# IPMC_MACP.net
KiCad netlist of a schematic drawn in Altium Designer
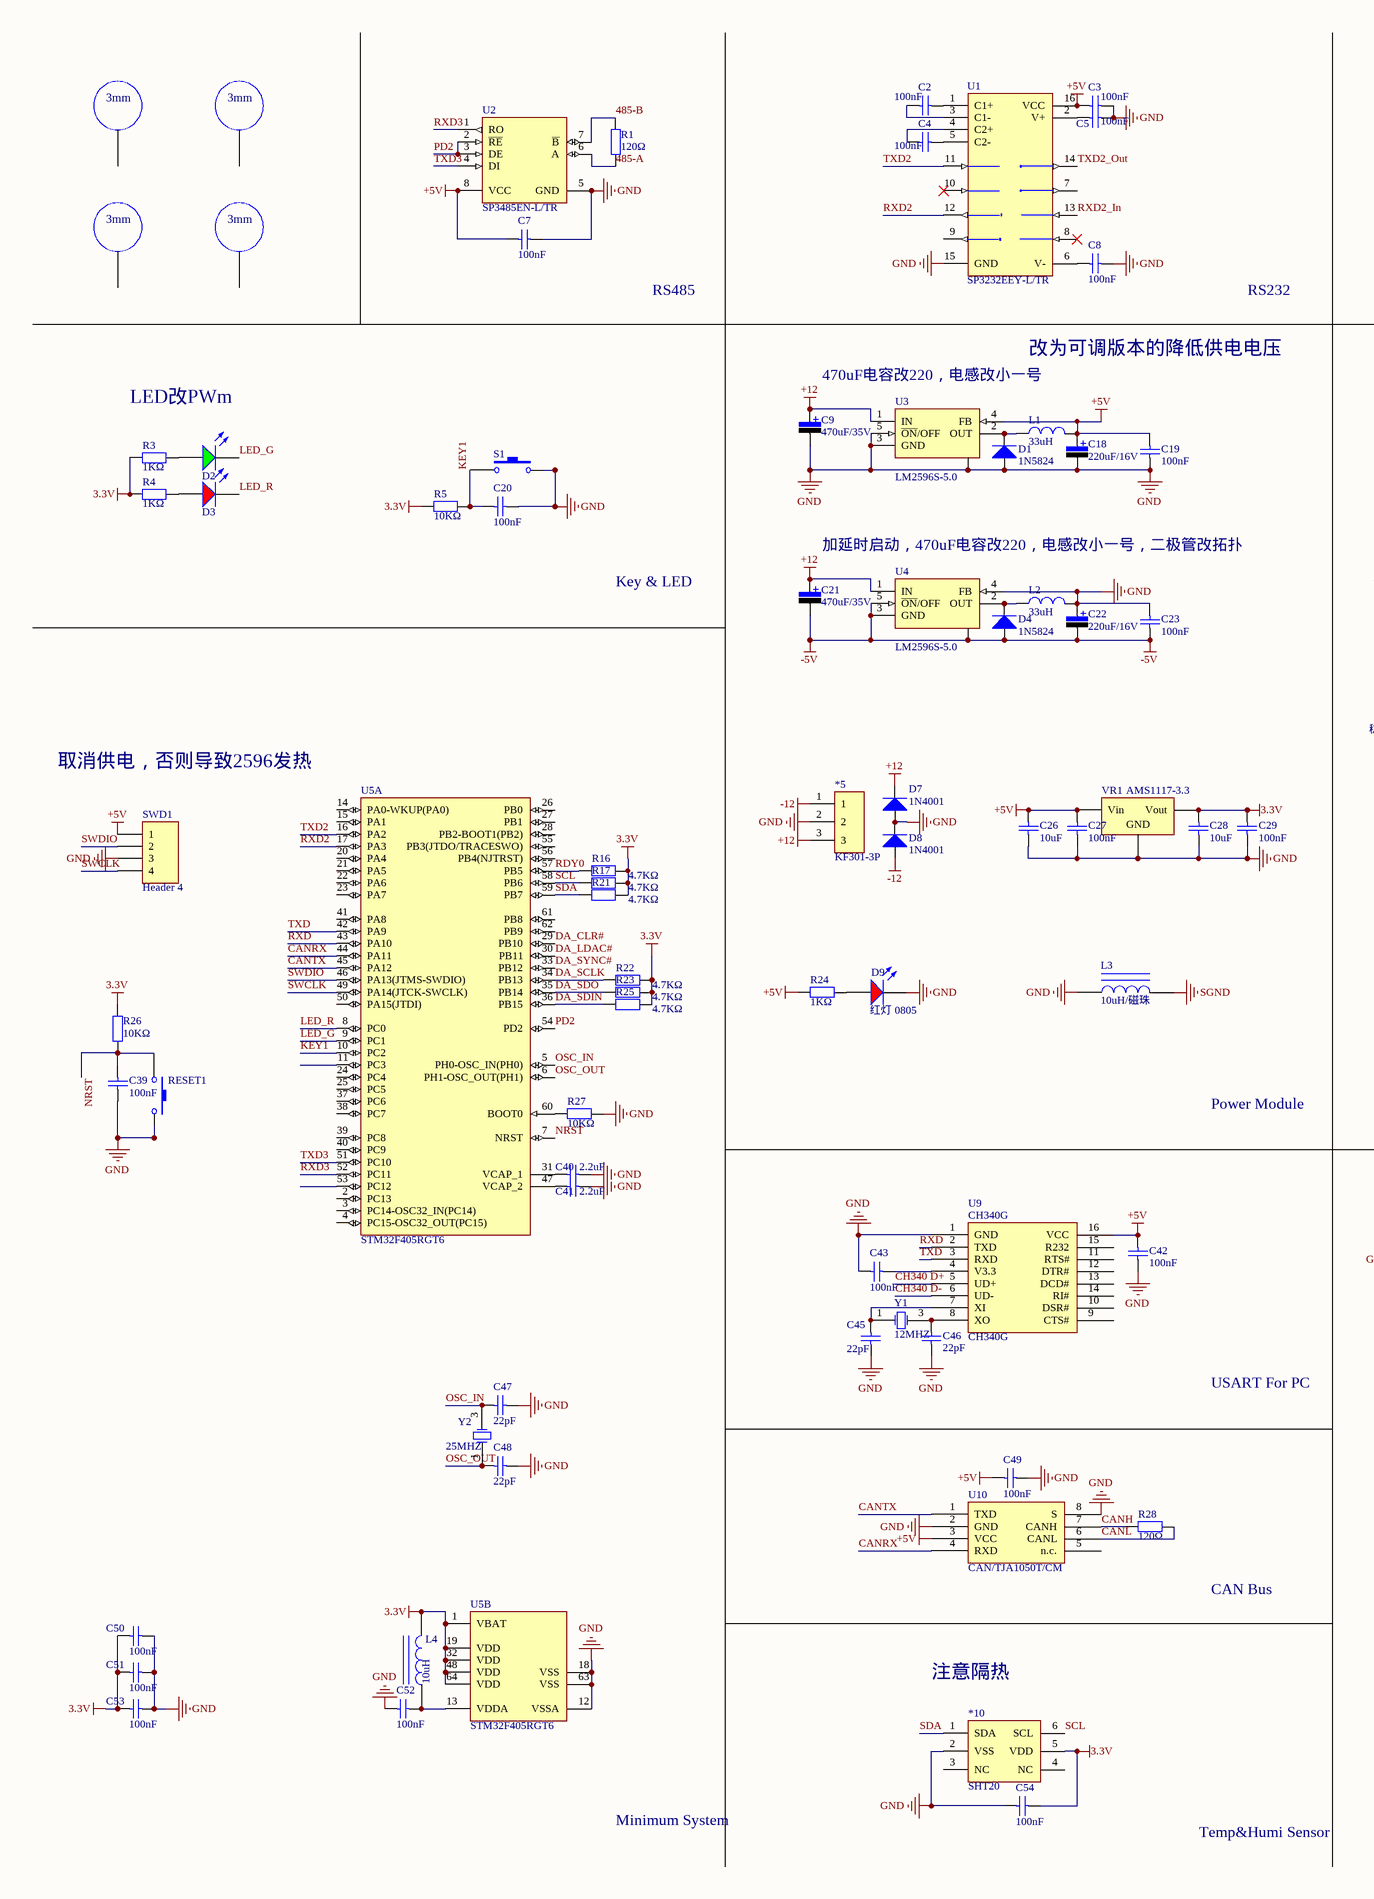
[diagram p0: IPMC_MACP.SchDoc, left]
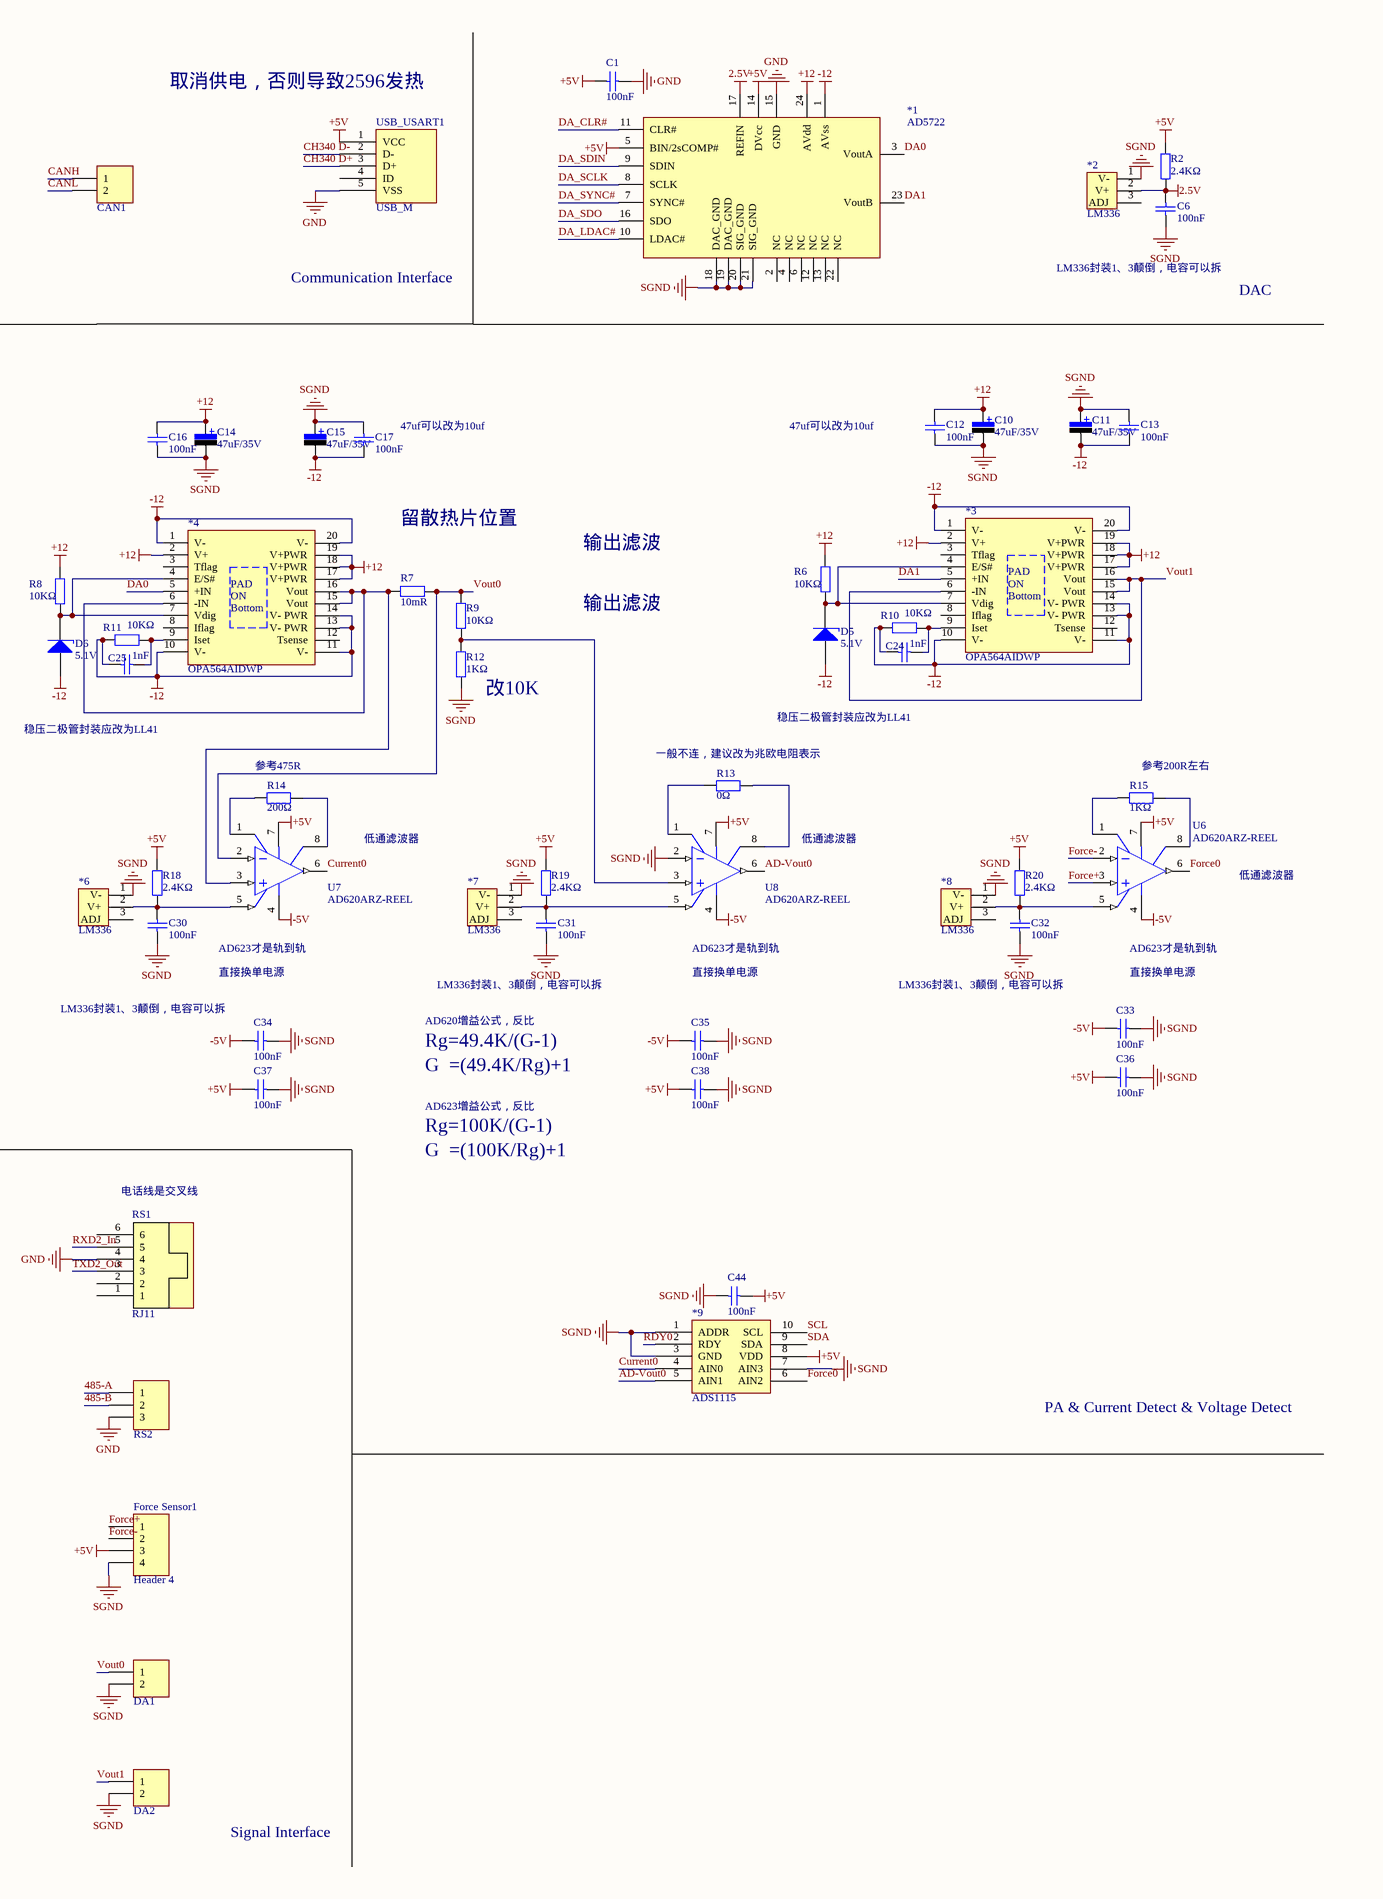
[diagram p1: IPMC_MACP.SchDoc, right]

(export (version "E")
  (design (tool "Eeschema 10.0.6"))
  (components
    (comp (ref "*1")
      (value "AD5722")
      (footprint "TSSOP24P")
      (description "双极性DAC")
      (libsource (lib "fszhang") (part "AD5722"))
    )
    (comp (ref "*2")
      (value "LM336")
      (footprint "TO-92A")
      (description "基准电压芯片2.5/5V")
      (libsource (lib "fszhang") (part "LM336"))
    )
    (comp (ref "*3")
      (value "OPA564AIDWP")
      (footprint "HSOP20")
      (description "PAD on Bottom")
      (libsource (lib "fszhang") (part "OPA564AIDWP"))
    )
    (comp (ref "*4")
      (value "OPA564AIDWP")
      (footprint "HSOP20")
      (description "PAD on Bottom")
      (libsource (lib "fszhang") (part "OPA564AIDWP"))
    )
    (comp (ref "*5")
      (value "KF301-3P")
      (footprint "KF301-3P")
      (description "蓝色端子")
      (libsource (lib "fszhang") (part "KF301-3P"))
    )
    (comp (ref "*6")
      (value "LM336")
      (footprint "TO-92A")
      (description "基准电压芯片2.5/5V")
      (libsource (lib "fszhang") (part "LM336"))
    )
    (comp (ref "*7")
      (value "LM336")
      (footprint "TO-92A")
      (description "基准电压芯片2.5/5V")
      (libsource (lib "fszhang") (part "LM336"))
    )
    (comp (ref "*8")
      (value "LM336")
      (footprint "TO-92A")
      (description "基准电压芯片2.5/5V")
      (libsource (lib "fszhang") (part "LM336"))
    )
    (comp (ref "*9") (value "ADS1115") (footprint "MSOP-UN10_N") (libsource (lib "fszhang") (part "ADS1115")))
    (comp (ref "*10") (value "SHT20") (footprint "DFN6") (libsource (lib "fszhang") (part "SHT20")))
    (comp (ref "C1")
      (value "100nF")
      (footprint "0805_C")
      (description "贴片电容")
      (libsource (lib "Miscellaneous Devices LC") (part "0805 100nF(104) 10% 50V"))
    )
    (comp (ref "C2")
      (value "100nF")
      (footprint "0805_C")
      (description "贴片电容")
      (libsource (lib "Miscellaneous Devices LC") (part "0805 100nF(104) 10% 50V"))
    )
    (comp (ref "C3")
      (value "100nF")
      (footprint "0805_C")
      (description "贴片电容")
      (libsource (lib "Miscellaneous Devices LC") (part "0805 100nF(104) 10% 50V"))
    )
    (comp (ref "C4")
      (value "100nF")
      (footprint "0805_C")
      (description "贴片电容")
      (libsource (lib "Miscellaneous Devices LC") (part "0805 100nF(104) 10% 50V"))
    )
    (comp (ref "C5")
      (value "100nF")
      (footprint "0805_C")
      (description "贴片电容")
      (libsource (lib "Miscellaneous Devices LC") (part "0805 100nF(104) 10% 50V"))
    )
    (comp (ref "C6")
      (value "100nF")
      (footprint "0805_C")
      (description "贴片电容")
      (libsource (lib "Miscellaneous Devices LC") (part "0805 100nF(104) 10% 50V"))
    )
    (comp (ref "C7")
      (value "100nF")
      (footprint "0805_C")
      (description "贴片电容")
      (libsource (lib "Miscellaneous Devices LC") (part "0805 100nF(104) 10% 50V"))
    )
    (comp (ref "C8")
      (value "100nF")
      (footprint "0805_C")
      (description "贴片电容")
      (libsource (lib "Miscellaneous Devices LC") (part "0805 100nF(104) 10% 50V"))
    )
    (comp (ref "C9")
      (value "470uF/35V")
      (footprint "C-RB-S10")
      (description "极性电解电容")
      (fields (field (name "PUBLISHER") "Altium Limited"))
      (libsource (lib "fszhang") (part "Cap Pol"))
    )
    (comp (ref "C10")
      (value "47uF/35V")
      (footprint "C-RB-S6")
      (description "极性电解电容")
      (fields (field (name "PUBLISHER") "Altium Limited"))
      (libsource (lib "fszhang") (part "Cap Pol"))
    )
    (comp (ref "C11")
      (value "47uF/35V")
      (footprint "C-RB-S6")
      (description "极性电解电容")
      (fields (field (name "PUBLISHER") "Altium Limited"))
      (libsource (lib "fszhang") (part "Cap Pol"))
    )
    (comp (ref "C12")
      (value "100nF")
      (footprint "0805_C")
      (description "贴片电容")
      (libsource (lib "Miscellaneous Devices LC") (part "0805 100nF(104) 10% 50V"))
    )
    (comp (ref "C13")
      (value "100nF")
      (footprint "0805_C")
      (description "贴片电容")
      (libsource (lib "Miscellaneous Devices LC") (part "0805 100nF(104) 10% 50V"))
    )
    (comp (ref "C14")
      (value "47uF/35V")
      (footprint "C-RB-S6")
      (description "极性电解电容")
      (fields (field (name "PUBLISHER") "Altium Limited"))
      (libsource (lib "fszhang") (part "Cap Pol"))
    )
    (comp (ref "C15")
      (value "47uF/35V")
      (footprint "C-RB-S6")
      (description "极性电解电容")
      (fields (field (name "PUBLISHER") "Altium Limited"))
      (libsource (lib "fszhang") (part "Cap Pol"))
    )
    (comp (ref "C16")
      (value "100nF")
      (footprint "0805_C")
      (description "贴片电容")
      (libsource (lib "Miscellaneous Devices LC") (part "0805 100nF(104) 10% 50V"))
    )
    (comp (ref "C17")
      (value "100nF")
      (footprint "0805_C")
      (description "贴片电容")
      (libsource (lib "Miscellaneous Devices LC") (part "0805 100nF(104) 10% 50V"))
    )
    (comp (ref "C18")
      (value "220uF/16V")
      (footprint "C-RB-S6")
      (description "极性电解电容")
      (fields (field (name "PUBLISHER") "Altium Limited"))
      (libsource (lib "fszhang") (part "Cap Pol"))
    )
    (comp (ref "C19")
      (value "100nF")
      (footprint "0805_C")
      (description "贴片电容")
      (libsource (lib "Miscellaneous Devices LC") (part "0805 100nF(104) 10% 50V"))
    )
    (comp (ref "C20")
      (value "100nF")
      (footprint "0805_C")
      (description "贴片电容")
      (libsource (lib "Miscellaneous Devices LC") (part "0805 100nF(104) 10% 50V"))
    )
    (comp (ref "C21")
      (value "470uF/35V")
      (footprint "C-RB-S10")
      (description "极性电解电容")
      (fields (field (name "PUBLISHER") "Altium Limited"))
      (libsource (lib "fszhang") (part "Cap Pol"))
    )
    (comp (ref "C22")
      (value "220uF/16V")
      (footprint "C-RB-S6")
      (description "极性电解电容")
      (fields (field (name "PUBLISHER") "Altium Limited"))
      (libsource (lib "fszhang") (part "Cap Pol"))
    )
    (comp (ref "C23")
      (value "100nF")
      (footprint "0805_C")
      (description "贴片电容")
      (libsource (lib "Miscellaneous Devices LC") (part "0805 100nF(104) 10% 50V"))
    )
    (comp (ref "C24")
      (value "1nF")
      (footprint "0805_C")
      (description "贴片电容")
      (libsource (lib "Miscellaneous Devices LC") (part "0805 1nF (102) 10% 50V"))
    )
    (comp (ref "C25")
      (value "1nF")
      (footprint "0805_C")
      (description "贴片电容")
      (libsource (lib "Miscellaneous Devices LC") (part "0805 1nF (102) 10% 50V"))
    )
    (comp (ref "C26")
      (value "10uF")
      (footprint "0805_C")
      (description "贴片电容")
      (libsource (lib "Miscellaneous Devices LC") (part "0805 10uF (106) 10% 25V"))
    )
    (comp (ref "C27")
      (value "100nF")
      (footprint "0805_C")
      (description "贴片电容")
      (libsource (lib "Miscellaneous Devices LC") (part "0805 100nF(104) 10% 50V"))
    )
    (comp (ref "C28")
      (value "10uF")
      (footprint "0805_C")
      (description "贴片电容")
      (libsource (lib "Miscellaneous Devices LC") (part "0805 10uF (106) 10% 25V"))
    )
    (comp (ref "C29")
      (value "100nF")
      (footprint "0805_C")
      (description "贴片电容")
      (libsource (lib "Miscellaneous Devices LC") (part "0805 100nF(104) 10% 50V"))
    )
    (comp (ref "C30")
      (value "100nF")
      (footprint "0805_C")
      (description "贴片电容")
      (libsource (lib "Miscellaneous Devices LC") (part "0805 100nF(104) 10% 50V"))
    )
    (comp (ref "C31")
      (value "100nF")
      (footprint "0805_C")
      (description "贴片电容")
      (libsource (lib "Miscellaneous Devices LC") (part "0805 100nF(104) 10% 50V"))
    )
    (comp (ref "C32")
      (value "100nF")
      (footprint "0805_C")
      (description "贴片电容")
      (libsource (lib "Miscellaneous Devices LC") (part "0805 100nF(104) 10% 50V"))
    )
    (comp (ref "C33")
      (value "100nF")
      (footprint "0805_C")
      (description "贴片电容")
      (libsource (lib "Miscellaneous Devices LC") (part "0805 100nF(104) 10% 50V"))
    )
    (comp (ref "C34")
      (value "100nF")
      (footprint "0805_C")
      (description "贴片电容")
      (libsource (lib "Miscellaneous Devices LC") (part "0805 100nF(104) 10% 50V"))
    )
    (comp (ref "C35")
      (value "100nF")
      (footprint "0805_C")
      (description "贴片电容")
      (libsource (lib "Miscellaneous Devices LC") (part "0805 100nF(104) 10% 50V"))
    )
    (comp (ref "C36")
      (value "100nF")
      (footprint "0805_C")
      (description "贴片电容")
      (libsource (lib "Miscellaneous Devices LC") (part "0805 100nF(104) 10% 50V"))
    )
    (comp (ref "C37")
      (value "100nF")
      (footprint "0805_C")
      (description "贴片电容")
      (libsource (lib "Miscellaneous Devices LC") (part "0805 100nF(104) 10% 50V"))
    )
    (comp (ref "C38")
      (value "100nF")
      (footprint "0805_C")
      (description "贴片电容")
      (libsource (lib "Miscellaneous Devices LC") (part "0805 100nF(104) 10% 50V"))
    )
    (comp (ref "C39")
      (value "100nF")
      (footprint "0805_C")
      (description "贴片电容")
      (libsource (lib "Miscellaneous Devices LC") (part "0805 100nF(104) 10% 50V"))
    )
    (comp (ref "C40")
      (value "2.2uF")
      (footprint "0805_C")
      (description "贴片电容")
      (libsource (lib "Miscellaneous Devices LC") (part "0805 2.2uF (225) 20% 50V"))
    )
    (comp (ref "C41")
      (value "2.2uF")
      (footprint "0805_C")
      (description "贴片电容")
      (libsource (lib "Miscellaneous Devices LC") (part "0805 2.2uF (225) 20% 50V"))
    )
    (comp (ref "C42")
      (value "100nF")
      (footprint "0805_C")
      (description "贴片电容")
      (libsource (lib "Miscellaneous Devices LC") (part "0805 100nF(104) 10% 50V"))
    )
    (comp (ref "C43")
      (value "100nF")
      (footprint "0805_C")
      (description "贴片电容")
      (libsource (lib "Miscellaneous Devices LC") (part "0805 100nF(104) 10% 50V"))
    )
    (comp (ref "C44")
      (value "100nF")
      (footprint "0805_C")
      (description "贴片电容")
      (libsource (lib "Miscellaneous Devices LC") (part "0805 100nF(104) 10% 50V"))
    )
    (comp (ref "C45")
      (value "22pF")
      (footprint "0805_C")
      (description "贴片电容")
      (libsource (lib "Miscellaneous Devices LC") (part "0805 22pF (220) 5% 50V"))
    )
    (comp (ref "C46")
      (value "22pF")
      (footprint "0805_C")
      (description "贴片电容")
      (libsource (lib "Miscellaneous Devices LC") (part "0805 22pF (220) 5% 50V"))
    )
    (comp (ref "C47")
      (value "22pF")
      (footprint "0805_C")
      (description "贴片电容")
      (libsource (lib "Miscellaneous Devices LC") (part "0805 22pF (220) 5% 50V"))
    )
    (comp (ref "C48")
      (value "22pF")
      (footprint "0805_C")
      (description "贴片电容")
      (libsource (lib "Miscellaneous Devices LC") (part "0805 22pF (220) 5% 50V"))
    )
    (comp (ref "C49")
      (value "100nF")
      (footprint "0805_C")
      (description "贴片电容")
      (libsource (lib "Miscellaneous Devices LC") (part "0805 100nF(104) 10% 50V"))
    )
    (comp (ref "C50")
      (value "100nF")
      (footprint "0805_C")
      (description "贴片电容")
      (libsource (lib "Miscellaneous Devices LC") (part "0805 100nF(104) 10% 50V"))
    )
    (comp (ref "C51")
      (value "100nF")
      (footprint "0805_C")
      (description "贴片电容")
      (libsource (lib "Miscellaneous Devices LC") (part "0805 100nF(104) 10% 50V"))
    )
    (comp (ref "C52")
      (value "100nF")
      (footprint "0805_C")
      (description "贴片电容")
      (libsource (lib "Miscellaneous Devices LC") (part "0805 100nF(104) 10% 50V"))
    )
    (comp (ref "C53")
      (value "100nF")
      (footprint "0805_C")
      (description "贴片电容")
      (libsource (lib "Miscellaneous Devices LC") (part "0805 100nF(104) 10% 50V"))
    )
    (comp (ref "C54")
      (value "100nF")
      (footprint "0805_C")
      (description "贴片电容")
      (libsource (lib "Miscellaneous Devices LC") (part "0805 100nF(104) 10% 50V"))
    )
    (comp (ref "CAN1")
      (value "Header 2")
      (footprint "HDR2X1_B1")
      (description "接插件")
      (fields (field (name "PUBLISHER") "Altium Limited"))
      (libsource (lib "fszhang") (part "Header 2"))
    )
    (comp (ref "D1")
      (value "1N5824")
      (footprint "DIODE-SMA")
      (description "二极管")
      (fields (field (name "PUBLISHER") "Altium Limited"))
      (libsource (lib "fszhang") (part "Diode"))
    )
    (comp (ref "D2")
      (value "翠绿 0805")
      (footprint "0805_LED_S1")
      (description "发光二极管")
      (libsource (lib "Miscellaneous Devices LC") (part "0805 翠绿"))
    )
    (comp (ref "D3")
      (value "红灯 0805")
      (footprint "0805_LED_S1")
      (description "发光二极管")
      (libsource (lib "Miscellaneous Devices LC") (part "0805 红灯"))
    )
    (comp (ref "D4")
      (value "1N5824")
      (footprint "DIODE-SMA")
      (description "二极管")
      (fields (field (name "PUBLISHER") "Altium Limited"))
      (libsource (lib "fszhang") (part "Diode"))
    )
    (comp (ref "D5")
      (value "5.1V")
      (footprint "DIODE-1206")
      (description "稳压二极管")
      (fields (field (name "PUBLISHER") "Altium Limited"))
      (libsource (lib "fszhang") (part "Diode-Z"))
    )
    (comp (ref "D6")
      (value "5.1V")
      (footprint "DIODE-1206")
      (description "稳压二极管")
      (fields (field (name "PUBLISHER") "Altium Limited"))
      (libsource (lib "fszhang") (part "Diode-Z"))
    )
    (comp (ref "D7")
      (value "1N4001")
      (footprint "DIODE-SMA")
      (description "二极管")
      (fields (field (name "PUBLISHER") "Altium Limited"))
      (libsource (lib "fszhang") (part "Diode"))
    )
    (comp (ref "D8")
      (value "1N4001")
      (footprint "DIODE-SMA")
      (description "二极管")
      (fields (field (name "PUBLISHER") "Altium Limited"))
      (libsource (lib "fszhang") (part "Diode"))
    )
    (comp (ref "D9")
      (value "红灯 0805")
      (footprint "0805_LED_S1")
      (description "发光二极管")
      (libsource (lib "Miscellaneous Devices LC") (part "0805 红灯"))
    )
    (comp (ref "DA1")
      (value "Header 2")
      (footprint "HDR2X1_B1")
      (description "接插件")
      (fields (field (name "PUBLISHER") "Altium Limited"))
      (libsource (lib "fszhang") (part "Header 2"))
    )
    (comp (ref "DA2")
      (value "Header 2")
      (footprint "HDR2X1_B1")
      (description "接插件")
      (fields (field (name "PUBLISHER") "Altium Limited"))
      (libsource (lib "fszhang") (part "Header 2"))
    )
    (comp (ref "Force Sensor1")
      (value "Header 4")
      (footprint "fszhang:HDR4X1_B1")
      (description "Header, 4-Pin")
      (fields (field (name "PUBLISHER") "Altium Limited"))
      (libsource (lib "Miscellaneous Connectors") (part "Header 4"))
    )
    (comp (ref "L1")
      (value "33uH")
      (footprint "L-SMD-12")
      (description "电感")
      (fields (field (name "PUBLISHER") "Altium Limited"))
      (libsource (lib "fszhang") (part "Inductor"))
    )
    (comp (ref "L2")
      (value "33uH")
      (footprint "L-SMD-12")
      (description "电感")
      (fields (field (name "PUBLISHER") "Altium Limited"))
      (libsource (lib "fszhang") (part "Inductor"))
    )
    (comp (ref "L3")
      (value "10uH/磁珠")
      (footprint "0805_L")
      (description "贴片电感")
      (libsource (lib "Miscellaneous Devices LC") (part "0805 10uH 10%"))
    )
    (comp (ref "L4")
      (value "10uH")
      (footprint "0805_L")
      (description "贴片电感")
      (libsource (lib "Miscellaneous Devices LC") (part "0805 10uH 10%"))
    )
    (comp (ref "R1")
      (value "120Ω")
      (footprint "0805_R")
      (description "贴片电阻")
      (libsource (lib "") (part "0805 120Ω (1200) 1%_1"))
    )
    (comp (ref "R2")
      (value "2.4KΩ")
      (footprint "0805_R")
      (description "贴片电阻")
      (libsource (lib "Miscellaneous Devices LC") (part "0805 2.4KΩ (2401) 1%"))
    )
    (comp (ref "R3")
      (value "1KΩ")
      (footprint "0805_R")
      (description "贴片电阻")
      (libsource (lib "Miscellaneous Devices LC") (part "0805 1KΩ (1001) 1%"))
    )
    (comp (ref "R4")
      (value "1KΩ")
      (footprint "0805_R")
      (description "贴片电阻")
      (libsource (lib "Miscellaneous Devices LC") (part "0805 1KΩ (1001) 1%"))
    )
    (comp (ref "R5")
      (value "10KΩ")
      (footprint "0805_R")
      (description "贴片电阻")
      (libsource (lib "Miscellaneous Devices LC") (part "0805 10KΩ (1002) 1%"))
    )
    (comp (ref "R6")
      (value "10KΩ")
      (footprint "0805_R")
      (description "贴片电阻")
      (libsource (lib "") (part "0805 10KΩ (1002) 1%_3"))
    )
    (comp (ref "R7")
      (value "10mR")
      (footprint "2512")
      (description "贴片电阻")
      (fields (field (name "PUBLISHER") "Altium Limited"))
      (libsource (lib "fszhang") (part "Res1"))
    )
    (comp (ref "R8")
      (value "10KΩ")
      (footprint "0805_R")
      (description "贴片电阻")
      (libsource (lib "") (part "0805 10KΩ (1002) 1%_3"))
    )
    (comp (ref "R9")
      (value "10KΩ")
      (footprint "0805_R")
      (description "贴片电阻")
      (libsource (lib "Miscellaneous Devices LC") (part "0805 20KΩ (2002) 1%"))
    )
    (comp (ref "R10")
      (value "10KΩ")
      (footprint "0805_R")
      (description "贴片电阻")
      (libsource (lib "Miscellaneous Devices LC") (part "0805 10KΩ (1002) 1%"))
    )
    (comp (ref "R11")
      (value "10KΩ")
      (footprint "0805_R")
      (description "贴片电阻")
      (libsource (lib "Miscellaneous Devices LC") (part "0805 10KΩ (1002) 1%"))
    )
    (comp (ref "R12")
      (value "1KΩ")
      (footprint "0805_R")
      (description "贴片电阻")
      (libsource (lib "Miscellaneous Devices LC") (part "0805 20KΩ (2002) 1%"))
    )
    (comp (ref "R13")
      (value "0Ω")
      (footprint "0805_R")
      (description "贴片电阻")
      (libsource (lib "Miscellaneous Devices LC") (part "0805 0Ω (0R0) 1%"))
    )
    (comp (ref "R14")
      (value "200Ω")
      (footprint "0805_R")
      (description "贴片电阻")
      (libsource (lib "Miscellaneous Devices LC") (part "0805 200Ω (2000) 1%"))
    )
    (comp (ref "R15")
      (value "1KΩ")
      (footprint "0805_R")
      (description "贴片电阻")
      (libsource (lib "Miscellaneous Devices LC") (part "0805 1KΩ (1001) 1%"))
    )
    (comp (ref "R16")
      (value "4.7KΩ")
      (footprint "0805_R")
      (description "贴片电阻")
      (libsource (lib "Miscellaneous Devices LC") (part "0805 4.7KΩ (4701) 1%"))
    )
    (comp (ref "R17")
      (value "4.7KΩ")
      (footprint "0805_R")
      (description "贴片电阻")
      (libsource (lib "Miscellaneous Devices LC") (part "0805 4.7KΩ (4701) 1%"))
    )
    (comp (ref "R18")
      (value "2.4KΩ")
      (footprint "0805_R")
      (description "贴片电阻")
      (libsource (lib "Miscellaneous Devices LC") (part "0805 2.4KΩ (2401) 1%"))
    )
    (comp (ref "R19")
      (value "2.4KΩ")
      (footprint "0805_R")
      (description "贴片电阻")
      (libsource (lib "Miscellaneous Devices LC") (part "0805 2.4KΩ (2401) 1%"))
    )
    (comp (ref "R20")
      (value "2.4KΩ")
      (footprint "0805_R")
      (description "贴片电阻")
      (libsource (lib "Miscellaneous Devices LC") (part "0805 2.4KΩ (2401) 1%"))
    )
    (comp (ref "R21")
      (value "4.7KΩ")
      (footprint "0805_R")
      (description "贴片电阻")
      (libsource (lib "Miscellaneous Devices LC") (part "0805 4.7KΩ (4701) 1%"))
    )
    (comp (ref "R22")
      (value "4.7KΩ")
      (footprint "0805_R")
      (description "贴片电阻")
      (libsource (lib "Miscellaneous Devices LC") (part "0805 4.7KΩ (4701) 1%"))
    )
    (comp (ref "R23")
      (value "4.7KΩ")
      (footprint "0805_R")
      (description "贴片电阻")
      (libsource (lib "Miscellaneous Devices LC") (part "0805 4.7KΩ (4701) 1%"))
    )
    (comp (ref "R24")
      (value "1KΩ")
      (footprint "0805_R")
      (description "贴片电阻")
      (libsource (lib "Miscellaneous Devices LC") (part "0805 1KΩ (1001) 1%"))
    )
    (comp (ref "R25")
      (value "4.7KΩ")
      (footprint "0805_R")
      (description "贴片电阻")
      (libsource (lib "Miscellaneous Devices LC") (part "0805 4.7KΩ (4701) 1%"))
    )
    (comp (ref "R26")
      (value "10KΩ")
      (footprint "0805_R")
      (description "贴片电阻")
      (libsource (lib "") (part "0805 10KΩ (1002) 1%_1"))
    )
    (comp (ref "R27")
      (value "10KΩ")
      (footprint "0805_R")
      (description "贴片电阻")
      (libsource (lib "") (part "0805 10KΩ (1002) 1%_2"))
    )
    (comp (ref "R28")
      (value "120Ω")
      (footprint "0805_R")
      (description "贴片电阻")
      (libsource (lib "Miscellaneous Devices LC") (part "0805 120Ω (1200) 1%"))
    )
    (comp (ref "RESET1")
      (value "SW-PB")
      (footprint "SW_PB2_A1")
      (description "微动开关")
      (fields (field (name "PUBLISHER") "Altium Limited"))
      (libsource (lib "fszhang") (part "SW-PB"))
    )
    (comp (ref "RS1") (value "RJ11") (footprint "RJ6-RJ11") (libsource (lib "fszhang") (part "RJ11")))
    (comp (ref "RS2")
      (value "Header 3")
      (footprint "HDR3X1_B1")
      (description "接插件")
      (fields (field (name "PUBLISHER") "Altium Limited"))
      (libsource (lib "fszhang") (part "Header 3"))
    )
    (comp (ref "S1")
      (value "SW-PB")
      (footprint "SW_PB2_A1")
      (description "微动开关")
      (fields (field (name "PUBLISHER") "Altium Limited"))
      (libsource (lib "fszhang") (part "SW-PB"))
    )
    (comp (ref "SWD1")
      (value "Header 4")
      (footprint "HDR1X4")
      (description "Header, 4-Pin")
      (fields (field (name "PUBLISHER") "Altium Limited"))
      (libsource (lib "Miscellaneous Connectors") (part "Header 4"))
    )
    (comp (ref "T1") (value "M3铜柱螺丝孔") (footprint "螺丝孔-3mm") (libsource (lib "fszhang") (part "M3铜柱螺丝孔")))
    (comp (ref "T2") (value "M3铜柱螺丝孔") (footprint "螺丝孔-3mm") (libsource (lib "fszhang") (part "M3铜柱螺丝孔")))
    (comp (ref "T3") (value "M3铜柱螺丝孔") (footprint "螺丝孔-3mm") (libsource (lib "fszhang") (part "M3铜柱螺丝孔")))
    (comp (ref "T4") (value "M3铜柱螺丝孔") (footprint "螺丝孔-3mm") (libsource (lib "fszhang") (part "M3铜柱螺丝孔")))
    (comp (ref "U1")
      (value "SP3232EEY-L/TR")
      (footprint "TSSOP-16")
      (description "RS232")
      (libsource (lib "Miscellaneous Devices LC") (part "SP3232EEY-L/TR"))
    )
    (comp (ref "U2")
      (value "SP3485EN-L/TR")
      (footprint "SOIC-8_150mil")
      (description "RS-485/RS-422")
      (libsource (lib "Miscellaneous Devices LC") (part "SP3485EN-L/TR"))
    )
    (comp (ref "U3")
      (value "LM2596S-5.0")
      (footprint "TO-263-5")
      (description "5V稳压芯片")
      (fields (field (name "PUBLISHER") "Altium Limited"))
      (libsource (lib "fszhang") (part "LM2596S-5.0"))
    )
    (comp (ref "U4")
      (value "LM2596S-5.0")
      (footprint "TO-263-5")
      (description "5V稳压芯片")
      (fields (field (name "PUBLISHER") "Altium Limited"))
      (libsource (lib "fszhang") (part "LM2596S-5.0"))
    )
    (comp (ref "U5")
      (value "STM32F405RGT6")
      (footprint "STM-LQFP64_L")
      (fields (field (name "MANUFACTURER") "STMicroelectronics"))
      (libsource (lib "STMicroelectronics STM32 F4") (part "STM32F405RGT6"))
    )
    (comp (ref "U6")
      (value "AD620ARZ-REEL")
      (footprint "SOIC-8_150mil")
      (description "仪放")
      (libsource (lib "Miscellaneous Devices LC") (part "AD620ARZ-REEL"))
    )
    (comp (ref "U7")
      (value "AD620ARZ-REEL")
      (footprint "SOIC-8_150mil")
      (description "仪放")
      (libsource (lib "Miscellaneous Devices LC") (part "AD620ARZ-REEL"))
    )
    (comp (ref "U8")
      (value "AD620ARZ-REEL")
      (footprint "SOIC-8_150mil")
      (description "仪放")
      (libsource (lib "Miscellaneous Devices LC") (part "AD620ARZ-REEL"))
    )
    (comp (ref "U9")
      (value "CH340G")
      (footprint "SOIC-16_150mil")
      (description "USB")
      (libsource (lib "Miscellaneous Devices LC") (part "CH340G"))
    )
    (comp (ref "U10")
      (value "CAN/TJA1050T/CM")
      (footprint "SOIC-8_150mil")
      (description "CAN")
      (libsource (lib "Miscellaneous Devices LC") (part "CAN/TJA1050T/CM"))
    )
    (comp (ref "USB_USART1")
      (value "USB_M")
      (footprint "USB_MICRO")
      (description "MicroUSB接口")
      (libsource (lib "fszhang") (part "USB_M"))
    )
    (comp (ref "VR1")
      (value "AMS1117-3.3")
      (footprint "SOT-223")
      (description "低压差线性稳压(LDO)")
      (libsource (lib "Miscellaneous Devices LC") (part "SOT-223 AMS1117-3.3"))
    )
    (comp (ref "Y1")
      (value "12MHZ")
      (footprint "SMD-3225_4P")
      (description "贴片晶振")
      (libsource (lib "Miscellaneous Devices LC") (part "SMD-3225_4P  12MHZ 20PF 10PPM"))
    )
    (comp (ref "Y2")
      (value "25MHZ")
      (footprint "SMD-3225_4P")
      (description "贴片晶振")
      (libsource (lib "Miscellaneous Devices LC") (part "SMD-3225_4P  25MHZ 12PF 10PPM"))
    )
  )
  (nets
    (net (code "1") (name "+5V") (class "Default")
      (node (ref "*1") (pin "14") (pinfunction "DVcc_14") (pintype "passive"))
      (node (ref "*1") (pin "5") (pinfunction "BIN/2sCOMP#_5") (pintype "passive"))
      (node (ref "*9") (pin "8") (pinfunction "VDD_8") (pintype "passive"))
      (node (ref "C1") (pin "2") (pinfunction "2_2") (pintype "passive"))
      (node (ref "C18") (pin "1") (pinfunction "1_1") (pintype "passive"))
      (node (ref "C19") (pin "2") (pinfunction "2_2") (pintype "passive"))
      (node (ref "C26") (pin "2") (pinfunction "2_2") (pintype "passive"))
      (node (ref "C27") (pin "2") (pinfunction "2_2") (pintype "passive"))
      (node (ref "C3") (pin "1") (pinfunction "1_1") (pintype "passive"))
      (node (ref "C36") (pin "2") (pinfunction "2_2") (pintype "passive"))
      (node (ref "C37") (pin "2") (pinfunction "2_2") (pintype "passive"))
      (node (ref "C38") (pin "2") (pinfunction "2_2") (pintype "passive"))
      (node (ref "C42") (pin "2") (pinfunction "2_2") (pintype "passive"))
      (node (ref "C44") (pin "1") (pinfunction "1_1") (pintype "passive"))
      (node (ref "C49") (pin "2") (pinfunction "2_2") (pintype "passive"))
      (node (ref "C7") (pin "2") (pinfunction "2_2") (pintype "passive"))
      (node (ref "Force Sensor1") (pin "3") (pinfunction "3_3") (pintype "passive"))
      (node (ref "L1") (pin "2") (pinfunction "2_2") (pintype "passive"))
      (node (ref "R18") (pin "2") (pinfunction "2_2") (pintype "passive"))
      (node (ref "R19") (pin "2") (pinfunction "2_2") (pintype "passive"))
      (node (ref "R2") (pin "2") (pinfunction "2_2") (pintype "passive"))
      (node (ref "R20") (pin "2") (pinfunction "2_2") (pintype "passive"))
      (node (ref "R24") (pin "1") (pinfunction "1_1") (pintype "passive"))
      (node (ref "SWD1") (pin "1") (pinfunction "1_1") (pintype "passive"))
      (node (ref "U1") (pin "16") (pinfunction "VCC_16") (pintype "power_in"))
      (node (ref "U10") (pin "3") (pinfunction "VCC_3") (pintype "passive"))
      (node (ref "U2") (pin "8") (pinfunction "VCC_8") (pintype "power_in"))
      (node (ref "U3") (pin "4") (pinfunction "FB_4") (pintype "input"))
      (node (ref "U6") (pin "7") (pinfunction "V+_7") (pintype "power_in"))
      (node (ref "U7") (pin "7") (pinfunction "V+_7") (pintype "power_in"))
      (node (ref "U8") (pin "7") (pinfunction "V+_7") (pintype "power_in"))
      (node (ref "U9") (pin "16") (pinfunction "VCC_16") (pintype "passive"))
      (node (ref "USB_USART1") (pin "1") (pinfunction "VCC_1") (pintype "passive"))
      (node (ref "VR1") (pin "3") (pinfunction "Vin_3") (pintype "passive"))
    )
    (net (code "2") (name "+12") (class "Default")
      (node (ref "*1") (pin "24") (pinfunction "AVdd_24") (pintype "passive"))
      (node (ref "*3") (pin "17") (pinfunction "V+PWR_17") (pintype "passive"))
      (node (ref "*3") (pin "18") (pinfunction "V+PWR_18") (pintype "passive"))
      (node (ref "*3") (pin "19") (pinfunction "V+PWR_19") (pintype "passive"))
      (node (ref "*3") (pin "2") (pinfunction "V+_2") (pintype "passive"))
      (node (ref "*4") (pin "17") (pinfunction "V+PWR_17") (pintype "passive"))
      (node (ref "*4") (pin "18") (pinfunction "V+PWR_18") (pintype "passive"))
      (node (ref "*4") (pin "19") (pinfunction "V+PWR_19") (pintype "passive"))
      (node (ref "*4") (pin "2") (pinfunction "V+_2") (pintype "passive"))
      (node (ref "*5") (pin "3") (pinfunction "3_3") (pintype "passive"))
      (node (ref "C10") (pin "1") (pinfunction "1_1") (pintype "passive"))
      (node (ref "C12") (pin "2") (pinfunction "2_2") (pintype "passive"))
      (node (ref "C14") (pin "1") (pinfunction "1_1") (pintype "passive"))
      (node (ref "C16") (pin "2") (pinfunction "2_2") (pintype "passive"))
      (node (ref "C21") (pin "1") (pinfunction "1_1") (pintype "passive"))
      (node (ref "C9") (pin "1") (pinfunction "1_1") (pintype "passive"))
      (node (ref "D7") (pin "2") (pinfunction "K_2") (pintype "passive"))
      (node (ref "R6") (pin "2") (pinfunction "2_2") (pintype "passive"))
      (node (ref "R8") (pin "2") (pinfunction "2_2") (pintype "passive"))
      (node (ref "U3") (pin "1") (pinfunction "IN_1") (pintype "power_in"))
      (node (ref "U4") (pin "1") (pinfunction "IN_1") (pintype "power_in"))
    )
    (net (code "3") (name "-5V") (class "Default")
      (node (ref "C21") (pin "2") (pinfunction "2_2") (pintype "passive"))
      (node (ref "C22") (pin "2") (pinfunction "2_2") (pintype "passive"))
      (node (ref "C23") (pin "1") (pinfunction "1_1") (pintype "passive"))
      (node (ref "C33") (pin "2") (pinfunction "2_2") (pintype "passive"))
      (node (ref "C34") (pin "2") (pinfunction "2_2") (pintype "passive"))
      (node (ref "C35") (pin "2") (pinfunction "2_2") (pintype "passive"))
      (node (ref "D4") (pin "1") (pinfunction "A_1") (pintype "passive"))
      (node (ref "U4") (pin "3") (pinfunction "GND_3") (pintype "power_in"))
      (node (ref "U4") (pin "5") (pinfunction "~{ON}/OFF_5") (pintype "input"))
      (node (ref "U4") (pin "6") (pinfunction "6_6") (pintype "power_in"))
      (node (ref "U6") (pin "4") (pinfunction "V-_4") (pintype "power_in"))
      (node (ref "U7") (pin "4") (pinfunction "V-_4") (pintype "power_in"))
      (node (ref "U8") (pin "4") (pinfunction "V-_4") (pintype "power_in"))
    )
    (net (code "4") (name "-12") (class "Default")
      (node (ref "*1") (pin "1") (pinfunction "AVss_1") (pintype "passive"))
      (node (ref "*3") (pin "1") (pinfunction "V-_1") (pintype "passive"))
      (node (ref "*3") (pin "10") (pinfunction "V-_10") (pintype "passive"))
      (node (ref "*3") (pin "11") (pinfunction "V-_11") (pintype "passive"))
      (node (ref "*3") (pin "13") (pinfunction "V-_PWR_13") (pintype "passive"))
      (node (ref "*3") (pin "14") (pinfunction "V-_PWR_14") (pintype "passive"))
      (node (ref "*3") (pin "20") (pinfunction "V-_20") (pintype "passive"))
      (node (ref "*4") (pin "1") (pinfunction "V-_1") (pintype "passive"))
      (node (ref "*4") (pin "10") (pinfunction "V-_10") (pintype "passive"))
      (node (ref "*4") (pin "11") (pinfunction "V-_11") (pintype "passive"))
      (node (ref "*4") (pin "13") (pinfunction "V-_PWR_13") (pintype "passive"))
      (node (ref "*4") (pin "14") (pinfunction "V-_PWR_14") (pintype "passive"))
      (node (ref "*4") (pin "20") (pinfunction "V-_20") (pintype "passive"))
      (node (ref "*5") (pin "1") (pinfunction "1_1") (pintype "passive"))
      (node (ref "C11") (pin "2") (pinfunction "2_2") (pintype "passive"))
      (node (ref "C13") (pin "2") (pinfunction "2_2") (pintype "passive"))
      (node (ref "C15") (pin "2") (pinfunction "2_2") (pintype "passive"))
      (node (ref "C17") (pin "2") (pinfunction "2_2") (pintype "passive"))
      (node (ref "C24") (pin "1") (pinfunction "1_1") (pintype "passive"))
      (node (ref "C25") (pin "1") (pinfunction "1_1") (pintype "passive"))
      (node (ref "D5") (pin "1") (pinfunction "A_1") (pintype "passive"))
      (node (ref "D6") (pin "1") (pinfunction "A_1") (pintype "passive"))
      (node (ref "D8") (pin "1") (pinfunction "A_1") (pintype "passive"))
      (node (ref "R10") (pin "1") (pinfunction "1_1") (pintype "passive"))
      (node (ref "R11") (pin "1") (pinfunction "1_1") (pintype "passive"))
    )
    (net (code "5") (name "/485-A") (class "Default")
      (node (ref "R1") (pin "1") (pinfunction "1_1") (pintype "passive"))
      (node (ref "RS2") (pin "1") (pinfunction "1_1") (pintype "passive"))
      (node (ref "U2") (pin "6") (pinfunction "A_6") (pintype "bidirectional"))
    )
    (net (code "6") (name "/485-B") (class "Default")
      (node (ref "R1") (pin "2") (pinfunction "2_2") (pintype "passive"))
      (node (ref "RS2") (pin "2") (pinfunction "2_2") (pintype "passive"))
      (node (ref "U2") (pin "7") (pinfunction "~{B}_7") (pintype "bidirectional"))
    )
    (net (code "7") (name "/AD-Vout0") (class "Default")
      (node (ref "*9") (pin "5") (pinfunction "AIN1_5") (pintype "passive"))
      (node (ref "U8") (pin "6") (pinfunction "OUT_6") (pintype "output"))
    )
    (net (code "8") (name "/CANH") (class "Default")
      (node (ref "CAN1") (pin "1") (pinfunction "1_1") (pintype "passive"))
      (node (ref "R28") (pin "1") (pinfunction "1_1") (pintype "passive"))
      (node (ref "U10") (pin "7") (pinfunction "CANH_7") (pintype "passive"))
    )
    (net (code "9") (name "/CANL") (class "Default")
      (node (ref "CAN1") (pin "2") (pinfunction "2_2") (pintype "passive"))
      (node (ref "R28") (pin "2") (pinfunction "2_2") (pintype "passive"))
      (node (ref "U10") (pin "6") (pinfunction "CANL_6") (pintype "passive"))
    )
    (net (code "10") (name "/CANRX") (class "Default")
      (node (ref "U10") (pin "4") (pinfunction "RXD_4") (pintype "passive"))
      (node (ref "U5") (pin "44") (pinfunction "PA11_44") (pintype "bidirectional"))
    )
    (net (code "11") (name "/CANTX") (class "Default")
      (node (ref "U10") (pin "1") (pinfunction "TXD_1") (pintype "passive"))
      (node (ref "U5") (pin "45") (pinfunction "PA12_45") (pintype "bidirectional"))
    )
    (net (code "12") (name "/CH340 D+") (class "Default")
      (node (ref "U9") (pin "5") (pinfunction "UD+_5") (pintype "passive"))
      (node (ref "USB_USART1") (pin "3") (pinfunction "D+_3") (pintype "passive"))
    )
    (net (code "13") (name "/CH340 D-") (class "Default")
      (node (ref "U9") (pin "6") (pinfunction "UD-_6") (pintype "passive"))
      (node (ref "USB_USART1") (pin "2") (pinfunction "D-_2") (pintype "passive"))
    )
    (net (code "14") (name "/Current0") (class "Default")
      (node (ref "*9") (pin "4") (pinfunction "AIN0_4") (pintype "passive"))
      (node (ref "U7") (pin "6") (pinfunction "OUT_6") (pintype "output"))
    )
    (net (code "15") (name "/DA0") (class "Default")
      (node (ref "*1") (pin "3") (pinfunction "VoutA_3") (pintype "passive"))
      (node (ref "*4") (pin "5") (pinfunction "+IN_5") (pintype "passive"))
    )
    (net (code "16") (name "/DA1") (class "Default")
      (node (ref "*1") (pin "23") (pinfunction "VoutB_23") (pintype "passive"))
      (node (ref "*3") (pin "5") (pinfunction "+IN_5") (pintype "passive"))
    )
    (net (code "17") (name "/DA_CLR#") (class "Default")
      (node (ref "*1") (pin "11") (pinfunction "CLR#_11") (pintype "passive"))
      (node (ref "U5") (pin "29") (pinfunction "PB10_29") (pintype "bidirectional"))
    )
    (net (code "18") (name "/DA_LDAC#") (class "Default")
      (node (ref "*1") (pin "10") (pinfunction "LDAC#_10") (pintype "passive"))
      (node (ref "U5") (pin "30") (pinfunction "PB11_30") (pintype "bidirectional"))
    )
    (net (code "19") (name "/DA_SCLK") (class "Default")
      (node (ref "*1") (pin "8") (pinfunction "SCLK_8") (pintype "passive"))
      (node (ref "R22") (pin "1") (pinfunction "1_1") (pintype "passive"))
      (node (ref "U5") (pin "34") (pinfunction "PB13_34") (pintype "bidirectional"))
    )
    (net (code "20") (name "/DA_SDIN") (class "Default")
      (node (ref "*1") (pin "9") (pinfunction "SDIN_9") (pintype "passive"))
      (node (ref "R25") (pin "1") (pinfunction "1_1") (pintype "passive"))
      (node (ref "U5") (pin "36") (pinfunction "PB15_36") (pintype "bidirectional"))
    )
    (net (code "21") (name "/DA_SDO") (class "Default")
      (node (ref "*1") (pin "16") (pinfunction "SDO_16") (pintype "passive"))
      (node (ref "R23") (pin "1") (pinfunction "1_1") (pintype "passive"))
      (node (ref "U5") (pin "35") (pinfunction "PB14_35") (pintype "bidirectional"))
    )
    (net (code "22") (name "/DA_SYNC#") (class "Default")
      (node (ref "*1") (pin "7") (pinfunction "SYNC#_7") (pintype "passive"))
      (node (ref "U5") (pin "33") (pinfunction "PB12_33") (pintype "bidirectional"))
    )
    (net (code "23") (name "/Force+") (class "Default")
      (node (ref "Force Sensor1") (pin "1") (pinfunction "1_1") (pintype "passive"))
      (node (ref "U6") (pin "3") (pinfunction "+IN_3") (pintype "input"))
    )
    (net (code "24") (name "/Force-") (class "Default")
      (node (ref "Force Sensor1") (pin "2") (pinfunction "2_2") (pintype "passive"))
      (node (ref "U6") (pin "2") (pinfunction "-IN_2") (pintype "input"))
    )
    (net (code "25") (name "/Force0") (class "Default")
      (node (ref "*9") (pin "6") (pinfunction "AIN2_6") (pintype "passive"))
      (node (ref "U6") (pin "6") (pinfunction "OUT_6") (pintype "output"))
    )
    (net (code "26") (name "/KEY1") (class "Default")
      (node (ref "C20") (pin "1") (pinfunction "1_1") (pintype "passive"))
      (node (ref "R5") (pin "2") (pinfunction "2_2") (pintype "passive"))
      (node (ref "S1") (pin "1") (pinfunction "1_1") (pintype "passive"))
      (node (ref "U5") (pin "10") (pinfunction "PC2_10") (pintype "bidirectional"))
    )
    (net (code "27") (name "/LED_G") (class "Default")
      (node (ref "D2") (pin "K") (pinfunction "K_K") (pintype "passive"))
      (node (ref "U5") (pin "9") (pinfunction "PC1_9") (pintype "bidirectional"))
    )
    (net (code "28") (name "/LED_R") (class "Default")
      (node (ref "D3") (pin "K") (pinfunction "K_K") (pintype "passive"))
      (node (ref "U5") (pin "8") (pinfunction "PC0_8") (pintype "bidirectional"))
    )
    (net (code "29") (name "/NRST") (class "Default")
      (node (ref "C39") (pin "1") (pinfunction "1_1") (pintype "passive"))
      (node (ref "R26") (pin "2") (pinfunction "2_2") (pintype "passive"))
      (node (ref "RESET1") (pin "1") (pinfunction "1_1") (pintype "passive"))
      (node (ref "U5") (pin "7") (pinfunction "NRST_7") (pintype "bidirectional"))
    )
    (net (code "30") (name "/OSC_IN") (class "Default")
      (node (ref "C47") (pin "2") (pinfunction "2_2") (pintype "passive"))
      (node (ref "U5") (pin "5") (pinfunction "PH0-OSC_IN(PH0)_5") (pintype "bidirectional"))
      (node (ref "Y2") (pin "3") (pinfunction "OSC2_3") (pintype "passive"))
    )
    (net (code "31") (name "/OSC_OUT") (class "Default")
      (node (ref "C48") (pin "2") (pinfunction "2_2") (pintype "passive"))
      (node (ref "U5") (pin "6") (pinfunction "PH1-OSC_OUT(PH1)_6") (pintype "bidirectional"))
      (node (ref "Y2") (pin "1") (pinfunction "OSC1_1") (pintype "passive"))
    )
    (net (code "32") (name "/PD2") (class "Default")
      (node (ref "U2") (pin "2") (pinfunction "~{RE}_2") (pintype "input"))
      (node (ref "U2") (pin "3") (pinfunction "DE_3") (pintype "input"))
      (node (ref "U5") (pin "54") (pinfunction "PD2_54") (pintype "bidirectional"))
    )
    (net (code "33") (name "/RDY0") (class "Default")
      (node (ref "*9") (pin "2") (pinfunction "RDY_2") (pintype "passive"))
      (node (ref "R16") (pin "1") (pinfunction "1_1") (pintype "passive"))
      (node (ref "U5") (pin "57") (pinfunction "PB5_57") (pintype "bidirectional"))
    )
    (net (code "34") (name "/RXD") (class "Default")
      (node (ref "U5") (pin "43") (pinfunction "PA10_43") (pintype "bidirectional"))
      (node (ref "U9") (pin "2") (pinfunction "TXD_2") (pintype "passive"))
    )
    (net (code "35") (name "/RXD2") (class "Default")
      (node (ref "U1") (pin "12") (pinfunction "R1OUT_12") (pintype "output"))
      (node (ref "U5") (pin "17") (pinfunction "PA3_17") (pintype "bidirectional"))
    )
    (net (code "36") (name "/RXD2_In") (class "Default")
      (node (ref "RS1") (pin "5") (pinfunction "5_5") (pintype "passive"))
      (node (ref "U1") (pin "13") (pinfunction "R1IN_13") (pintype "input"))
    )
    (net (code "37") (name "/RXD3") (class "Default")
      (node (ref "U2") (pin "1") (pinfunction "RO_1") (pintype "output"))
      (node (ref "U5") (pin "52") (pinfunction "PC11_52") (pintype "bidirectional"))
    )
    (net (code "38") (name "/SCL") (class "Default")
      (node (ref "*10") (pin "6") (pinfunction "SCL_6") (pintype "passive"))
      (node (ref "*9") (pin "10") (pinfunction "SCL_10") (pintype "passive"))
      (node (ref "R17") (pin "1") (pinfunction "1_1") (pintype "passive"))
      (node (ref "U5") (pin "58") (pinfunction "PB6_58") (pintype "bidirectional"))
    )
    (net (code "39") (name "/SDA") (class "Default")
      (node (ref "*10") (pin "1") (pinfunction "SDA_1") (pintype "passive"))
      (node (ref "*9") (pin "9") (pinfunction "SDA_9") (pintype "passive"))
      (node (ref "R21") (pin "1") (pinfunction "1_1") (pintype "passive"))
      (node (ref "U5") (pin "59") (pinfunction "PB7_59") (pintype "bidirectional"))
    )
    (net (code "40") (name "/SWCLK") (class "Default")
      (node (ref "SWD1") (pin "4") (pinfunction "4_4") (pintype "passive"))
      (node (ref "U5") (pin "49") (pinfunction "PA14(JTCK-SWCLK)_49") (pintype "bidirectional"))
    )
    (net (code "41") (name "/SWDIO") (class "Default")
      (node (ref "SWD1") (pin "2") (pinfunction "2_2") (pintype "passive"))
      (node (ref "U5") (pin "46") (pinfunction "PA13(JTMS-SWDIO)_46") (pintype "bidirectional"))
    )
    (net (code "42") (name "/TXD") (class "Default")
      (node (ref "U5") (pin "42") (pinfunction "PA9_42") (pintype "bidirectional"))
      (node (ref "U9") (pin "3") (pinfunction "RXD_3") (pintype "passive"))
    )
    (net (code "43") (name "/TXD2") (class "Default")
      (node (ref "U1") (pin "11") (pinfunction "T1IN_11") (pintype "input"))
      (node (ref "U5") (pin "16") (pinfunction "PA2_16") (pintype "bidirectional"))
    )
    (net (code "44") (name "/TXD2_Out") (class "Default")
      (node (ref "RS1") (pin "3") (pinfunction "3_3") (pintype "passive"))
      (node (ref "U1") (pin "14") (pinfunction "T1OUT_14") (pintype "output"))
    )
    (net (code "45") (name "/TXD3") (class "Default")
      (node (ref "U2") (pin "4") (pinfunction "DI_4") (pintype "input"))
      (node (ref "U5") (pin "51") (pinfunction "PC10_51") (pintype "bidirectional"))
    )
    (net (code "46") (name "/Vout0") (class "Default")
      (node (ref "DA1") (pin "1") (pinfunction "1_1") (pintype "passive"))
      (node (ref "R7") (pin "2") (pinfunction "2_2") (pintype "passive"))
      (node (ref "R9") (pin "1") (pinfunction "1_1") (pintype "passive"))
      (node (ref "U7") (pin "2") (pinfunction "-IN_2") (pintype "input"))
    )
    (net (code "47") (name "/Vout1") (class "Default")
      (node (ref "*3") (pin "15") (pinfunction "Vout_15") (pintype "passive"))
      (node (ref "*3") (pin "16") (pinfunction "Vout_16") (pintype "passive"))
      (node (ref "*3") (pin "6") (pinfunction "-IN_6") (pintype "passive"))
      (node (ref "DA2") (pin "1") (pinfunction "1_1") (pintype "passive"))
    )
    (net (code "48") (name "2.5V") (class "Default")
      (node (ref "*1") (pin "17") (pinfunction "REFIN_17") (pintype "passive"))
      (node (ref "*2") (pin "2") (pinfunction "V+_2") (pintype "passive"))
      (node (ref "C6") (pin "2") (pinfunction "2_2") (pintype "passive"))
      (node (ref "R2") (pin "1") (pinfunction "1_1") (pintype "passive"))
    )
    (net (code "49") (name "3.3V") (class "Default")
      (node (ref "*10") (pin "5") (pinfunction "VDD_5") (pintype "passive"))
      (node (ref "C28") (pin "2") (pinfunction "2_2") (pintype "passive"))
      (node (ref "C29") (pin "2") (pinfunction "2_2") (pintype "passive"))
      (node (ref "C50") (pin "1") (pinfunction "1_1") (pintype "passive"))
      (node (ref "C51") (pin "1") (pinfunction "1_1") (pintype "passive"))
      (node (ref "C53") (pin "1") (pinfunction "1_1") (pintype "passive"))
      (node (ref "C54") (pin "1") (pinfunction "1_1") (pintype "passive"))
      (node (ref "L4") (pin "2") (pinfunction "2_2") (pintype "passive"))
      (node (ref "R16") (pin "2") (pinfunction "2_2") (pintype "passive"))
      (node (ref "R17") (pin "2") (pinfunction "2_2") (pintype "passive"))
      (node (ref "R21") (pin "2") (pinfunction "2_2") (pintype "passive"))
      (node (ref "R22") (pin "2") (pinfunction "2_2") (pintype "passive"))
      (node (ref "R23") (pin "2") (pinfunction "2_2") (pintype "passive"))
      (node (ref "R25") (pin "2") (pinfunction "2_2") (pintype "passive"))
      (node (ref "R26") (pin "1") (pinfunction "1_1") (pintype "passive"))
      (node (ref "R3") (pin "1") (pinfunction "1_1") (pintype "passive"))
      (node (ref "R4") (pin "1") (pinfunction "1_1") (pintype "passive"))
      (node (ref "R5") (pin "1") (pinfunction "1_1") (pintype "passive"))
      (node (ref "U5") (pin "1") (pinfunction "VBAT_1") (pintype "power_in"))
      (node (ref "U5") (pin "19") (pinfunction "VDD_19") (pintype "power_in"))
      (node (ref "U5") (pin "32") (pinfunction "VDD_32") (pintype "power_in"))
      (node (ref "U5") (pin "48") (pinfunction "VDD_48") (pintype "power_in"))
      (node (ref "U5") (pin "64") (pinfunction "VDD_64") (pintype "power_in"))
      (node (ref "VR1") (pin "2") (pinfunction "Vout_2") (pintype "passive"))
    )
    (net (code "50") (name "GND") (class "Default")
      (node (ref "*1") (pin "15") (pinfunction "GND_15") (pintype "passive"))
      (node (ref "*10") (pin "2") (pinfunction "VSS_2") (pintype "passive"))
      (node (ref "*5") (pin "2") (pinfunction "2_2") (pintype "passive"))
      (node (ref "C1") (pin "1") (pinfunction "1_1") (pintype "passive"))
      (node (ref "C18") (pin "2") (pinfunction "2_2") (pintype "passive"))
      (node (ref "C19") (pin "1") (pinfunction "1_1") (pintype "passive"))
      (node (ref "C20") (pin "2") (pinfunction "2_2") (pintype "passive"))
      (node (ref "C22") (pin "1") (pinfunction "1_1") (pintype "passive"))
      (node (ref "C23") (pin "2") (pinfunction "2_2") (pintype "passive"))
      (node (ref "C26") (pin "1") (pinfunction "1_1") (pintype "passive"))
      (node (ref "C27") (pin "1") (pinfunction "1_1") (pintype "passive"))
      (node (ref "C28") (pin "1") (pinfunction "1_1") (pintype "passive"))
      (node (ref "C29") (pin "1") (pinfunction "1_1") (pintype "passive"))
      (node (ref "C3") (pin "2") (pinfunction "2_2") (pintype "passive"))
      (node (ref "C39") (pin "2") (pinfunction "2_2") (pintype "passive"))
      (node (ref "C40") (pin "2") (pinfunction "2_2") (pintype "passive"))
      (node (ref "C41") (pin "2") (pinfunction "2_2") (pintype "passive"))
      (node (ref "C42") (pin "1") (pinfunction "1_1") (pintype "passive"))
      (node (ref "C43") (pin "2") (pinfunction "2_2") (pintype "passive"))
      (node (ref "C45") (pin "1") (pinfunction "1_1") (pintype "passive"))
      (node (ref "C46") (pin "1") (pinfunction "1_1") (pintype "passive"))
      (node (ref "C47") (pin "1") (pinfunction "1_1") (pintype "passive"))
      (node (ref "C48") (pin "1") (pinfunction "1_1") (pintype "passive"))
      (node (ref "C49") (pin "1") (pinfunction "1_1") (pintype "passive"))
      (node (ref "C5") (pin "2") (pinfunction "2_2") (pintype "passive"))
      (node (ref "C50") (pin "2") (pinfunction "2_2") (pintype "passive"))
      (node (ref "C51") (pin "2") (pinfunction "2_2") (pintype "passive"))
      (node (ref "C52") (pin "2") (pinfunction "2_2") (pintype "passive"))
      (node (ref "C53") (pin "2") (pinfunction "2_2") (pintype "passive"))
      (node (ref "C54") (pin "2") (pinfunction "2_2") (pintype "passive"))
      (node (ref "C7") (pin "1") (pinfunction "1_1") (pintype "passive"))
      (node (ref "C8") (pin "2") (pinfunction "2_2") (pintype "passive"))
      (node (ref "C9") (pin "2") (pinfunction "2_2") (pintype "passive"))
      (node (ref "D1") (pin "1") (pinfunction "A_1") (pintype "passive"))
      (node (ref "D7") (pin "1") (pinfunction "A_1") (pintype "passive"))
      (node (ref "D8") (pin "2") (pinfunction "K_2") (pintype "passive"))
      (node (ref "D9") (pin "K") (pinfunction "K_K") (pintype "passive"))
      (node (ref "L2") (pin "2") (pinfunction "2_2") (pintype "passive"))
      (node (ref "L3") (pin "1") (pinfunction "1_1") (pintype "passive"))
      (node (ref "R27") (pin "1") (pinfunction "1_1") (pintype "passive"))
      (node (ref "RESET1") (pin "2") (pinfunction "2_2") (pintype "passive"))
      (node (ref "RS1") (pin "4") (pinfunction "4_4") (pintype "passive"))
      (node (ref "RS2") (pin "3") (pinfunction "3_3") (pintype "passive"))
      (node (ref "S1") (pin "2") (pinfunction "2_2") (pintype "passive"))
      (node (ref "SWD1") (pin "3") (pinfunction "3_3") (pintype "passive"))
      (node (ref "U1") (pin "15") (pinfunction "GND_15") (pintype "power_in"))
      (node (ref "U10") (pin "2") (pinfunction "GND_2") (pintype "passive"))
      (node (ref "U10") (pin "8") (pinfunction "S_8") (pintype "passive"))
      (node (ref "U2") (pin "5") (pinfunction "GND_5") (pintype "power_in"))
      (node (ref "U3") (pin "3") (pinfunction "GND_3") (pintype "power_in"))
      (node (ref "U3") (pin "5") (pinfunction "~{ON}/OFF_5") (pintype "input"))
      (node (ref "U3") (pin "6") (pinfunction "6_6") (pintype "power_in"))
      (node (ref "U4") (pin "4") (pinfunction "FB_4") (pintype "input"))
      (node (ref "U5") (pin "12") (pinfunction "VSSA_12") (pintype "power_in"))
      (node (ref "U5") (pin "18") (pinfunction "VSS_18") (pintype "power_in"))
      (node (ref "U5") (pin "63") (pinfunction "VSS_63") (pintype "power_in"))
      (node (ref "U9") (pin "1") (pinfunction "GND_1") (pintype "passive"))
      (node (ref "USB_USART1") (pin "5") (pinfunction "VSS_5") (pintype "passive"))
      (node (ref "VR1") (pin "1") (pinfunction "GND_1") (pintype "passive"))
    )
    (net (code "51") (name "Net-(*3-E{slash}S#)") (class "Default")
      (node (ref "*3") (pin "4") (pinfunction "E/S#_4") (pintype "passive"))
      (node (ref "*3") (pin "7") (pinfunction "Vdig_7") (pintype "passive"))
      (node (ref "D5") (pin "2") (pinfunction "K_2") (pintype "passive"))
      (node (ref "R6") (pin "1") (pinfunction "1_1") (pintype "passive"))
    )
    (net (code "52") (name "Net-(*3-Iset)") (class "Default")
      (node (ref "*3") (pin "9") (pinfunction "Iset_9") (pintype "passive"))
      (node (ref "C24") (pin "2") (pinfunction "2_2") (pintype "passive"))
      (node (ref "R10") (pin "2") (pinfunction "2_2") (pintype "passive"))
    )
    (net (code "53") (name "Net-(*4--IN)") (class "Default")
      (node (ref "*4") (pin "15") (pinfunction "Vout_15") (pintype "passive"))
      (node (ref "*4") (pin "16") (pinfunction "Vout_16") (pintype "passive"))
      (node (ref "*4") (pin "6") (pinfunction "-IN_6") (pintype "passive"))
      (node (ref "R7") (pin "1") (pinfunction "1_1") (pintype "passive"))
      (node (ref "U7") (pin "3") (pinfunction "+IN_3") (pintype "input"))
    )
    (net (code "54") (name "Net-(*4-E{slash}S#)") (class "Default")
      (node (ref "*4") (pin "4") (pinfunction "E/S#_4") (pintype "passive"))
      (node (ref "*4") (pin "7") (pinfunction "Vdig_7") (pintype "passive"))
      (node (ref "D6") (pin "2") (pinfunction "K_2") (pintype "passive"))
      (node (ref "R8") (pin "1") (pinfunction "1_1") (pintype "passive"))
    )
    (net (code "55") (name "Net-(*4-Iset)") (class "Default")
      (node (ref "*4") (pin "9") (pinfunction "Iset_9") (pintype "passive"))
      (node (ref "C25") (pin "2") (pinfunction "2_2") (pintype "passive"))
      (node (ref "R11") (pin "2") (pinfunction "2_2") (pintype "passive"))
    )
    (net (code "56") (name "Net-(*6-V+)") (class "Default")
      (node (ref "*6") (pin "2") (pinfunction "V+_2") (pintype "passive"))
      (node (ref "C30") (pin "2") (pinfunction "2_2") (pintype "passive"))
      (node (ref "R18") (pin "1") (pinfunction "1_1") (pintype "passive"))
      (node (ref "U7") (pin "5") (pinfunction "REF_5") (pintype "input"))
    )
    (net (code "57") (name "Net-(*7-V+)") (class "Default")
      (node (ref "*7") (pin "2") (pinfunction "V+_2") (pintype "passive"))
      (node (ref "C31") (pin "2") (pinfunction "2_2") (pintype "passive"))
      (node (ref "R19") (pin "1") (pinfunction "1_1") (pintype "passive"))
      (node (ref "U8") (pin "5") (pinfunction "REF_5") (pintype "input"))
    )
    (net (code "58") (name "Net-(*8-V+)") (class "Default")
      (node (ref "*8") (pin "2") (pinfunction "V+_2") (pintype "passive"))
      (node (ref "C32") (pin "2") (pinfunction "2_2") (pintype "passive"))
      (node (ref "R20") (pin "1") (pinfunction "1_1") (pintype "passive"))
      (node (ref "U6") (pin "5") (pinfunction "REF_5") (pintype "input"))
    )
    (net (code "59") (name "Net-(D1-K)") (class "Default")
      (node (ref "D1") (pin "2") (pinfunction "K_2") (pintype "passive"))
      (node (ref "L1") (pin "1") (pinfunction "1_1") (pintype "passive"))
      (node (ref "U3") (pin "2") (pinfunction "OUT_2") (pintype "power_in"))
    )
    (net (code "60") (name "Net-(D2-PadA)") (class "Default")
      (node (ref "D2") (pin "A") (pinfunction "A_A") (pintype "passive"))
      (node (ref "R3") (pin "2") (pinfunction "2_2") (pintype "passive"))
    )
    (net (code "61") (name "Net-(D3-PadA)") (class "Default")
      (node (ref "D3") (pin "A") (pinfunction "A_A") (pintype "passive"))
      (node (ref "R4") (pin "2") (pinfunction "2_2") (pintype "passive"))
    )
    (net (code "62") (name "Net-(D4-K)") (class "Default")
      (node (ref "D4") (pin "2") (pinfunction "K_2") (pintype "passive"))
      (node (ref "L2") (pin "1") (pinfunction "1_1") (pintype "passive"))
      (node (ref "U4") (pin "2") (pinfunction "OUT_2") (pintype "power_in"))
    )
    (net (code "63") (name "Net-(D9-PadA)") (class "Default")
      (node (ref "D9") (pin "A") (pinfunction "A_A") (pintype "passive"))
      (node (ref "R24") (pin "2") (pinfunction "2_2") (pintype "passive"))
    )
    (net (code "64") (name "Net-(R13-Pad1)") (class "Default")
      (node (ref "R13") (pin "1") (pinfunction "1_1") (pintype "passive"))
      (node (ref "U8") (pin "1") (pinfunction "RG_1") (pintype "passive"))
    )
    (net (code "65") (name "Net-(R13-Pad2)") (class "Default")
      (node (ref "R13") (pin "2") (pinfunction "2_2") (pintype "passive"))
      (node (ref "U8") (pin "8") (pinfunction "RG_8") (pintype "passive"))
    )
    (net (code "66") (name "Net-(R14-Pad1)") (class "Default")
      (node (ref "R14") (pin "1") (pinfunction "1_1") (pintype "passive"))
      (node (ref "U7") (pin "1") (pinfunction "RG_1") (pintype "passive"))
    )
    (net (code "67") (name "Net-(R14-Pad2)") (class "Default")
      (node (ref "R14") (pin "2") (pinfunction "2_2") (pintype "passive"))
      (node (ref "U7") (pin "8") (pinfunction "RG_8") (pintype "passive"))
    )
    (net (code "68") (name "Net-(R15-Pad1)") (class "Default")
      (node (ref "R15") (pin "1") (pinfunction "1_1") (pintype "passive"))
      (node (ref "U6") (pin "1") (pinfunction "RG_1") (pintype "passive"))
    )
    (net (code "69") (name "Net-(R15-Pad2)") (class "Default")
      (node (ref "R15") (pin "2") (pinfunction "2_2") (pintype "passive"))
      (node (ref "U6") (pin "8") (pinfunction "RG_8") (pintype "passive"))
    )
    (net (code "70") (name "Net-(U1-C1+)") (class "Default")
      (node (ref "C2") (pin "2") (pinfunction "2_2") (pintype "passive"))
      (node (ref "U1") (pin "1") (pinfunction "C1+_1") (pintype "passive"))
    )
    (net (code "71") (name "Net-(U1-C1-)") (class "Default")
      (node (ref "C2") (pin "1") (pinfunction "1_1") (pintype "passive"))
      (node (ref "U1") (pin "3") (pinfunction "C1-_3") (pintype "passive"))
    )
    (net (code "72") (name "Net-(U1-C2+)") (class "Default")
      (node (ref "C4") (pin "1") (pinfunction "1_1") (pintype "passive"))
      (node (ref "U1") (pin "4") (pinfunction "C2+_4") (pintype "passive"))
    )
    (net (code "73") (name "Net-(U1-C2-)") (class "Default")
      (node (ref "C4") (pin "2") (pinfunction "2_2") (pintype "passive"))
      (node (ref "U1") (pin "5") (pinfunction "C2-_5") (pintype "passive"))
    )
    (net (code "74") (name "Net-(U1-V+)") (class "Default")
      (node (ref "C5") (pin "1") (pinfunction "1_1") (pintype "passive"))
      (node (ref "U1") (pin "2") (pinfunction "V+_2") (pintype "power_in"))
    )
    (net (code "75") (name "Net-(U1-V-)") (class "Default")
      (node (ref "C8") (pin "1") (pinfunction "1_1") (pintype "passive"))
      (node (ref "U1") (pin "6") (pinfunction "V-_6") (pintype "power_in"))
    )
    (net (code "76") (name "Net-(U5A-BOOT0)") (class "Default")
      (node (ref "R27") (pin "2") (pinfunction "2_2") (pintype "passive"))
      (node (ref "U5") (pin "60") (pinfunction "BOOT0_60") (pintype "input"))
    )
    (net (code "77") (name "Net-(U5A-VCAP_1)") (class "Default")
      (node (ref "C40") (pin "1") (pinfunction "1_1") (pintype "passive"))
      (node (ref "U5") (pin "31") (pinfunction "VCAP_1_31") (pintype "power_in"))
    )
    (net (code "78") (name "Net-(U5A-VCAP_2)") (class "Default")
      (node (ref "C41") (pin "1") (pinfunction "1_1") (pintype "passive"))
      (node (ref "U5") (pin "47") (pinfunction "VCAP_2_47") (pintype "power_in"))
    )
    (net (code "79") (name "Net-(U5B-VDDA)") (class "Default")
      (node (ref "C52") (pin "1") (pinfunction "1_1") (pintype "passive"))
      (node (ref "L4") (pin "1") (pinfunction "1_1") (pintype "passive"))
      (node (ref "U5") (pin "13") (pinfunction "VDDA_13") (pintype "power_in"))
    )
    (net (code "80") (name "Net-(U8-+IN)") (class "Default")
      (node (ref "R12") (pin "1") (pinfunction "1_1") (pintype "passive"))
      (node (ref "R9") (pin "2") (pinfunction "2_2") (pintype "passive"))
      (node (ref "U8") (pin "3") (pinfunction "+IN_3") (pintype "input"))
    )
    (net (code "81") (name "Net-(U9-V3.3)") (class "Default")
      (node (ref "C43") (pin "1") (pinfunction "1_1") (pintype "passive"))
      (node (ref "U9") (pin "4") (pinfunction "V3.3_4") (pintype "passive"))
    )
    (net (code "82") (name "Net-(U9-XI)") (class "Default")
      (node (ref "C45") (pin "2") (pinfunction "2_2") (pintype "passive"))
      (node (ref "U9") (pin "7") (pinfunction "XI_7") (pintype "passive"))
      (node (ref "Y1") (pin "1") (pinfunction "OSC1_1") (pintype "passive"))
    )
    (net (code "83") (name "Net-(U9-XO)") (class "Default")
      (node (ref "C46") (pin "2") (pinfunction "2_2") (pintype "passive"))
      (node (ref "U9") (pin "8") (pinfunction "XO_8") (pintype "passive"))
      (node (ref "Y1") (pin "3") (pinfunction "OSC2_3") (pintype "passive"))
    )
    (net (code "84") (name "SGND") (class "Default")
      (node (ref "*1") (pin "18") (pinfunction "DAC_GND_18") (pintype "passive"))
      (node (ref "*1") (pin "19") (pinfunction "DAC_GND_19") (pintype "passive"))
      (node (ref "*1") (pin "20") (pinfunction "SIG_GND_20") (pintype "passive"))
      (node (ref "*1") (pin "21") (pinfunction "SIG_GND_21") (pintype "passive"))
      (node (ref "*2") (pin "1") (pinfunction "V-_1") (pintype "passive"))
      (node (ref "*6") (pin "1") (pinfunction "V-_1") (pintype "passive"))
      (node (ref "*7") (pin "1") (pinfunction "V-_1") (pintype "passive"))
      (node (ref "*8") (pin "1") (pinfunction "V-_1") (pintype "passive"))
      (node (ref "*9") (pin "1") (pinfunction "ADDR_1") (pintype "passive"))
      (node (ref "*9") (pin "3") (pinfunction "GND_3") (pintype "passive"))
      (node (ref "*9") (pin "7") (pinfunction "AIN3_7") (pintype "passive"))
      (node (ref "C10") (pin "2") (pinfunction "2_2") (pintype "passive"))
      (node (ref "C11") (pin "1") (pinfunction "1_1") (pintype "passive"))
      (node (ref "C12") (pin "1") (pinfunction "1_1") (pintype "passive"))
      (node (ref "C13") (pin "1") (pinfunction "1_1") (pintype "passive"))
      (node (ref "C14") (pin "2") (pinfunction "2_2") (pintype "passive"))
      (node (ref "C15") (pin "1") (pinfunction "1_1") (pintype "passive"))
      (node (ref "C16") (pin "1") (pinfunction "1_1") (pintype "passive"))
      (node (ref "C17") (pin "1") (pinfunction "1_1") (pintype "passive"))
      (node (ref "C30") (pin "1") (pinfunction "1_1") (pintype "passive"))
      (node (ref "C31") (pin "1") (pinfunction "1_1") (pintype "passive"))
      (node (ref "C32") (pin "1") (pinfunction "1_1") (pintype "passive"))
      (node (ref "C33") (pin "1") (pinfunction "1_1") (pintype "passive"))
      (node (ref "C34") (pin "1") (pinfunction "1_1") (pintype "passive"))
      (node (ref "C35") (pin "1") (pinfunction "1_1") (pintype "passive"))
      (node (ref "C36") (pin "1") (pinfunction "1_1") (pintype "passive"))
      (node (ref "C37") (pin "1") (pinfunction "1_1") (pintype "passive"))
      (node (ref "C38") (pin "1") (pinfunction "1_1") (pintype "passive"))
      (node (ref "C44") (pin "2") (pinfunction "2_2") (pintype "passive"))
      (node (ref "C6") (pin "1") (pinfunction "1_1") (pintype "passive"))
      (node (ref "DA1") (pin "2") (pinfunction "2_2") (pintype "passive"))
      (node (ref "DA2") (pin "2") (pinfunction "2_2") (pintype "passive"))
      (node (ref "Force Sensor1") (pin "4") (pinfunction "4_4") (pintype "passive"))
      (node (ref "L3") (pin "2") (pinfunction "2_2") (pintype "passive"))
      (node (ref "R12") (pin "2") (pinfunction "2_2") (pintype "passive"))
      (node (ref "U8") (pin "2") (pinfunction "-IN_2") (pintype "input"))
    )
    (net (code "85") (name "unconnected-(*1-NC-Pad2)") (class "Default")
      (node (ref "*1") (pin "2") (pinfunction "NC_2") (pintype "passive"))
    )
    (net (code "86") (name "unconnected-(*1-NC-Pad4)") (class "Default")
      (node (ref "*1") (pin "4") (pinfunction "NC_4") (pintype "passive"))
    )
    (net (code "87") (name "unconnected-(*1-NC-Pad6)") (class "Default")
      (node (ref "*1") (pin "6") (pinfunction "NC_6") (pintype "passive"))
    )
    (net (code "88") (name "unconnected-(*1-NC-Pad12)") (class "Default")
      (node (ref "*1") (pin "12") (pinfunction "NC_12") (pintype "passive"))
    )
    (net (code "89") (name "unconnected-(*1-NC-Pad13)") (class "Default")
      (node (ref "*1") (pin "13") (pinfunction "NC_13") (pintype "passive"))
    )
    (net (code "90") (name "unconnected-(*1-NC-Pad22)") (class "Default")
      (node (ref "*1") (pin "22") (pinfunction "NC_22") (pintype "passive"))
    )
    (net (code "91") (name "unconnected-(*2-ADJ-Pad3)") (class "Default")
      (node (ref "*2") (pin "3") (pinfunction "ADJ_3") (pintype "passive"))
    )
    (net (code "92") (name "unconnected-(*3-Iflag-Pad8)") (class "Default")
      (node (ref "*3") (pin "8") (pinfunction "Iflag_8") (pintype "passive"))
    )
    (net (code "93") (name "unconnected-(*3-Tflag-Pad3)") (class "Default")
      (node (ref "*3") (pin "3") (pinfunction "Tflag_3") (pintype "passive"))
    )
    (net (code "94") (name "unconnected-(*3-Tsense-Pad12)") (class "Default")
      (node (ref "*3") (pin "12") (pinfunction "Tsense_12") (pintype "passive"))
    )
    (net (code "95") (name "unconnected-(*4-Iflag-Pad8)") (class "Default")
      (node (ref "*4") (pin "8") (pinfunction "Iflag_8") (pintype "passive"))
    )
    (net (code "96") (name "unconnected-(*4-Tflag-Pad3)") (class "Default")
      (node (ref "*4") (pin "3") (pinfunction "Tflag_3") (pintype "passive"))
    )
    (net (code "97") (name "unconnected-(*4-Tsense-Pad12)") (class "Default")
      (node (ref "*4") (pin "12") (pinfunction "Tsense_12") (pintype "passive"))
    )
    (net (code "98") (name "unconnected-(*6-ADJ-Pad3)") (class "Default")
      (node (ref "*6") (pin "3") (pinfunction "ADJ_3") (pintype "passive"))
    )
    (net (code "99") (name "unconnected-(*7-ADJ-Pad3)") (class "Default")
      (node (ref "*7") (pin "3") (pinfunction "ADJ_3") (pintype "passive"))
    )
    (net (code "100") (name "unconnected-(*8-ADJ-Pad3)") (class "Default")
      (node (ref "*8") (pin "3") (pinfunction "ADJ_3") (pintype "passive"))
    )
    (net (code "101") (name "unconnected-(*10-NC-Pad3)") (class "Default")
      (node (ref "*10") (pin "3") (pinfunction "NC_3") (pintype "passive"))
    )
    (net (code "102") (name "unconnected-(*10-NC-Pad4)") (class "Default")
      (node (ref "*10") (pin "4") (pinfunction "NC_4") (pintype "passive"))
    )
    (net (code "103") (name "unconnected-(RS1-Pad1)") (class "Default")
      (node (ref "RS1") (pin "1") (pinfunction "1_1") (pintype "passive"))
    )
    (net (code "104") (name "unconnected-(RS1-Pad2)") (class "Default")
      (node (ref "RS1") (pin "2") (pinfunction "2_2") (pintype "passive"))
    )
    (net (code "105") (name "unconnected-(RS1-Pad6)") (class "Default")
      (node (ref "RS1") (pin "6") (pinfunction "6_6") (pintype "passive"))
    )
    (net (code "106") (name "unconnected-(T1-Pad1)") (class "Default")
      (node (ref "T1") (pin "1") (pinfunction "1_1") (pintype "passive"))
    )
    (net (code "107") (name "unconnected-(T2-Pad1)") (class "Default")
      (node (ref "T2") (pin "1") (pinfunction "1_1") (pintype "passive"))
    )
    (net (code "108") (name "unconnected-(T3-Pad1)") (class "Default")
      (node (ref "T3") (pin "1") (pinfunction "1_1") (pintype "passive"))
    )
    (net (code "109") (name "unconnected-(T4-Pad1)") (class "Default")
      (node (ref "T4") (pin "1") (pinfunction "1_1") (pintype "passive"))
    )
    (net (code "110") (name "unconnected-(U1-R2IN-Pad8)") (class "Default")
      (node (ref "U1") (pin "8") (pinfunction "R2IN_8") (pintype "input+no_connect"))
    )
    (net (code "111") (name "unconnected-(U1-R2OUT-Pad9)") (class "Default")
      (node (ref "U1") (pin "9") (pinfunction "R2OUT_9") (pintype "output"))
    )
    (net (code "112") (name "unconnected-(U1-T2IN-Pad10)") (class "Default")
      (node (ref "U1") (pin "10") (pinfunction "T2IN_10") (pintype "input+no_connect"))
    )
    (net (code "113") (name "unconnected-(U1-T2OUT-Pad7)") (class "Default")
      (node (ref "U1") (pin "7") (pinfunction "T2OUT_7") (pintype "output"))
    )
    (net (code "114") (name "unconnected-(U5A-PA0-WKUP(PA0)-Pad14)") (class "Default")
      (node (ref "U5") (pin "14") (pinfunction "PA0-WKUP(PA0)_14") (pintype "bidirectional"))
    )
    (net (code "115") (name "unconnected-(U5A-PA1-Pad15)") (class "Default")
      (node (ref "U5") (pin "15") (pinfunction "PA1_15") (pintype "bidirectional"))
    )
    (net (code "116") (name "unconnected-(U5A-PA4-Pad20)") (class "Default")
      (node (ref "U5") (pin "20") (pinfunction "PA4_20") (pintype "bidirectional"))
    )
    (net (code "117") (name "unconnected-(U5A-PA5-Pad21)") (class "Default")
      (node (ref "U5") (pin "21") (pinfunction "PA5_21") (pintype "bidirectional"))
    )
    (net (code "118") (name "unconnected-(U5A-PA6-Pad22)") (class "Default")
      (node (ref "U5") (pin "22") (pinfunction "PA6_22") (pintype "bidirectional"))
    )
    (net (code "119") (name "unconnected-(U5A-PA7-Pad23)") (class "Default")
      (node (ref "U5") (pin "23") (pinfunction "PA7_23") (pintype "bidirectional"))
    )
    (net (code "120") (name "unconnected-(U5A-PA8-Pad41)") (class "Default")
      (node (ref "U5") (pin "41") (pinfunction "PA8_41") (pintype "bidirectional"))
    )
    (net (code "121") (name "unconnected-(U5A-PA15(JTDI)-Pad50)") (class "Default")
      (node (ref "U5") (pin "50") (pinfunction "PA15(JTDI)_50") (pintype "bidirectional"))
    )
    (net (code "122") (name "unconnected-(U5A-PB0-Pad26)") (class "Default")
      (node (ref "U5") (pin "26") (pinfunction "PB0_26") (pintype "bidirectional"))
    )
    (net (code "123") (name "unconnected-(U5A-PB1-Pad27)") (class "Default")
      (node (ref "U5") (pin "27") (pinfunction "PB1_27") (pintype "bidirectional"))
    )
    (net (code "124") (name "unconnected-(U5A-PB2-BOOT1(PB2)-Pad28)") (class "Default")
      (node (ref "U5") (pin "28") (pinfunction "PB2-BOOT1(PB2)_28") (pintype "bidirectional"))
    )
    (net (code "125") (name "unconnected-(U5A-PB3(JTDO{slash}TRACESWO)-Pad55)") (class "Default")
      (node (ref "U5") (pin "55") (pinfunction "PB3(JTDO/TRACESWO)_55") (pintype "bidirectional"))
    )
    (net (code "126") (name "unconnected-(U5A-PB4(NJTRST)-Pad56)") (class "Default")
      (node (ref "U5") (pin "56") (pinfunction "PB4(NJTRST)_56") (pintype "bidirectional"))
    )
    (net (code "127") (name "unconnected-(U5A-PB8-Pad61)") (class "Default")
      (node (ref "U5") (pin "61") (pinfunction "PB8_61") (pintype "bidirectional"))
    )
    (net (code "128") (name "unconnected-(U5A-PB9-Pad62)") (class "Default")
      (node (ref "U5") (pin "62") (pinfunction "PB9_62") (pintype "bidirectional"))
    )
    (net (code "129") (name "unconnected-(U5A-PC3-Pad11)") (class "Default")
      (node (ref "U5") (pin "11") (pinfunction "PC3_11") (pintype "bidirectional"))
    )
    (net (code "130") (name "unconnected-(U5A-PC4-Pad24)") (class "Default")
      (node (ref "U5") (pin "24") (pinfunction "PC4_24") (pintype "bidirectional"))
    )
    (net (code "131") (name "unconnected-(U5A-PC5-Pad25)") (class "Default")
      (node (ref "U5") (pin "25") (pinfunction "PC5_25") (pintype "bidirectional"))
    )
    (net (code "132") (name "unconnected-(U5A-PC6-Pad37)") (class "Default")
      (node (ref "U5") (pin "37") (pinfunction "PC6_37") (pintype "bidirectional"))
    )
    (net (code "133") (name "unconnected-(U5A-PC7-Pad38)") (class "Default")
      (node (ref "U5") (pin "38") (pinfunction "PC7_38") (pintype "bidirectional"))
    )
    (net (code "134") (name "unconnected-(U5A-PC8-Pad39)") (class "Default")
      (node (ref "U5") (pin "39") (pinfunction "PC8_39") (pintype "bidirectional"))
    )
    (net (code "135") (name "unconnected-(U5A-PC9-Pad40)") (class "Default")
      (node (ref "U5") (pin "40") (pinfunction "PC9_40") (pintype "bidirectional"))
    )
    (net (code "136") (name "unconnected-(U5A-PC12-Pad53)") (class "Default")
      (node (ref "U5") (pin "53") (pinfunction "PC12_53") (pintype "bidirectional"))
    )
    (net (code "137") (name "unconnected-(U5A-PC13-Pad2)") (class "Default")
      (node (ref "U5") (pin "2") (pinfunction "PC13_2") (pintype "bidirectional"))
    )
    (net (code "138") (name "unconnected-(U5A-PC14-OSC32_IN(PC14)-Pad3)") (class "Default")
      (node (ref "U5") (pin "3") (pinfunction "PC14-OSC32_IN(PC14)_3") (pintype "bidirectional"))
    )
    (net (code "139") (name "unconnected-(U5A-PC15-OSC32_OUT(PC15)-Pad4)") (class "Default")
      (node (ref "U5") (pin "4") (pinfunction "PC15-OSC32_OUT(PC15)_4") (pintype "bidirectional"))
    )
    (net (code "140") (name "unconnected-(U9-CTS#-Pad9)") (class "Default")
      (node (ref "U9") (pin "9") (pinfunction "CTS#_9") (pintype "passive"))
    )
    (net (code "141") (name "unconnected-(U9-DCD#-Pad13)") (class "Default")
      (node (ref "U9") (pin "13") (pinfunction "DCD#_13") (pintype "passive"))
    )
    (net (code "142") (name "unconnected-(U9-DSR#-Pad10)") (class "Default")
      (node (ref "U9") (pin "10") (pinfunction "DSR#_10") (pintype "passive"))
    )
    (net (code "143") (name "unconnected-(U9-DTR#-Pad12)") (class "Default")
      (node (ref "U9") (pin "12") (pinfunction "DTR#_12") (pintype "passive"))
    )
    (net (code "144") (name "unconnected-(U9-R232-Pad15)") (class "Default")
      (node (ref "U9") (pin "15") (pinfunction "R232_15") (pintype "passive"))
    )
    (net (code "145") (name "unconnected-(U9-RI#-Pad14)") (class "Default")
      (node (ref "U9") (pin "14") (pinfunction "RI#_14") (pintype "passive"))
    )
    (net (code "146") (name "unconnected-(U9-RTS#-Pad11)") (class "Default")
      (node (ref "U9") (pin "11") (pinfunction "RTS#_11") (pintype "passive"))
    )
    (net (code "147") (name "unconnected-(U10-n.c.-Pad5)") (class "Default")
      (node (ref "U10") (pin "5") (pinfunction "n.c._5") (pintype "passive"))
    )
    (net (code "148") (name "unconnected-(USB_USART1-ID-Pad4)") (class "Default")
      (node (ref "USB_USART1") (pin "4") (pinfunction "ID_4") (pintype "passive"))
    )
  )
)
